# PET_snes_gamepad.net
KiCad netlist of a schematic drawn in EAGLE
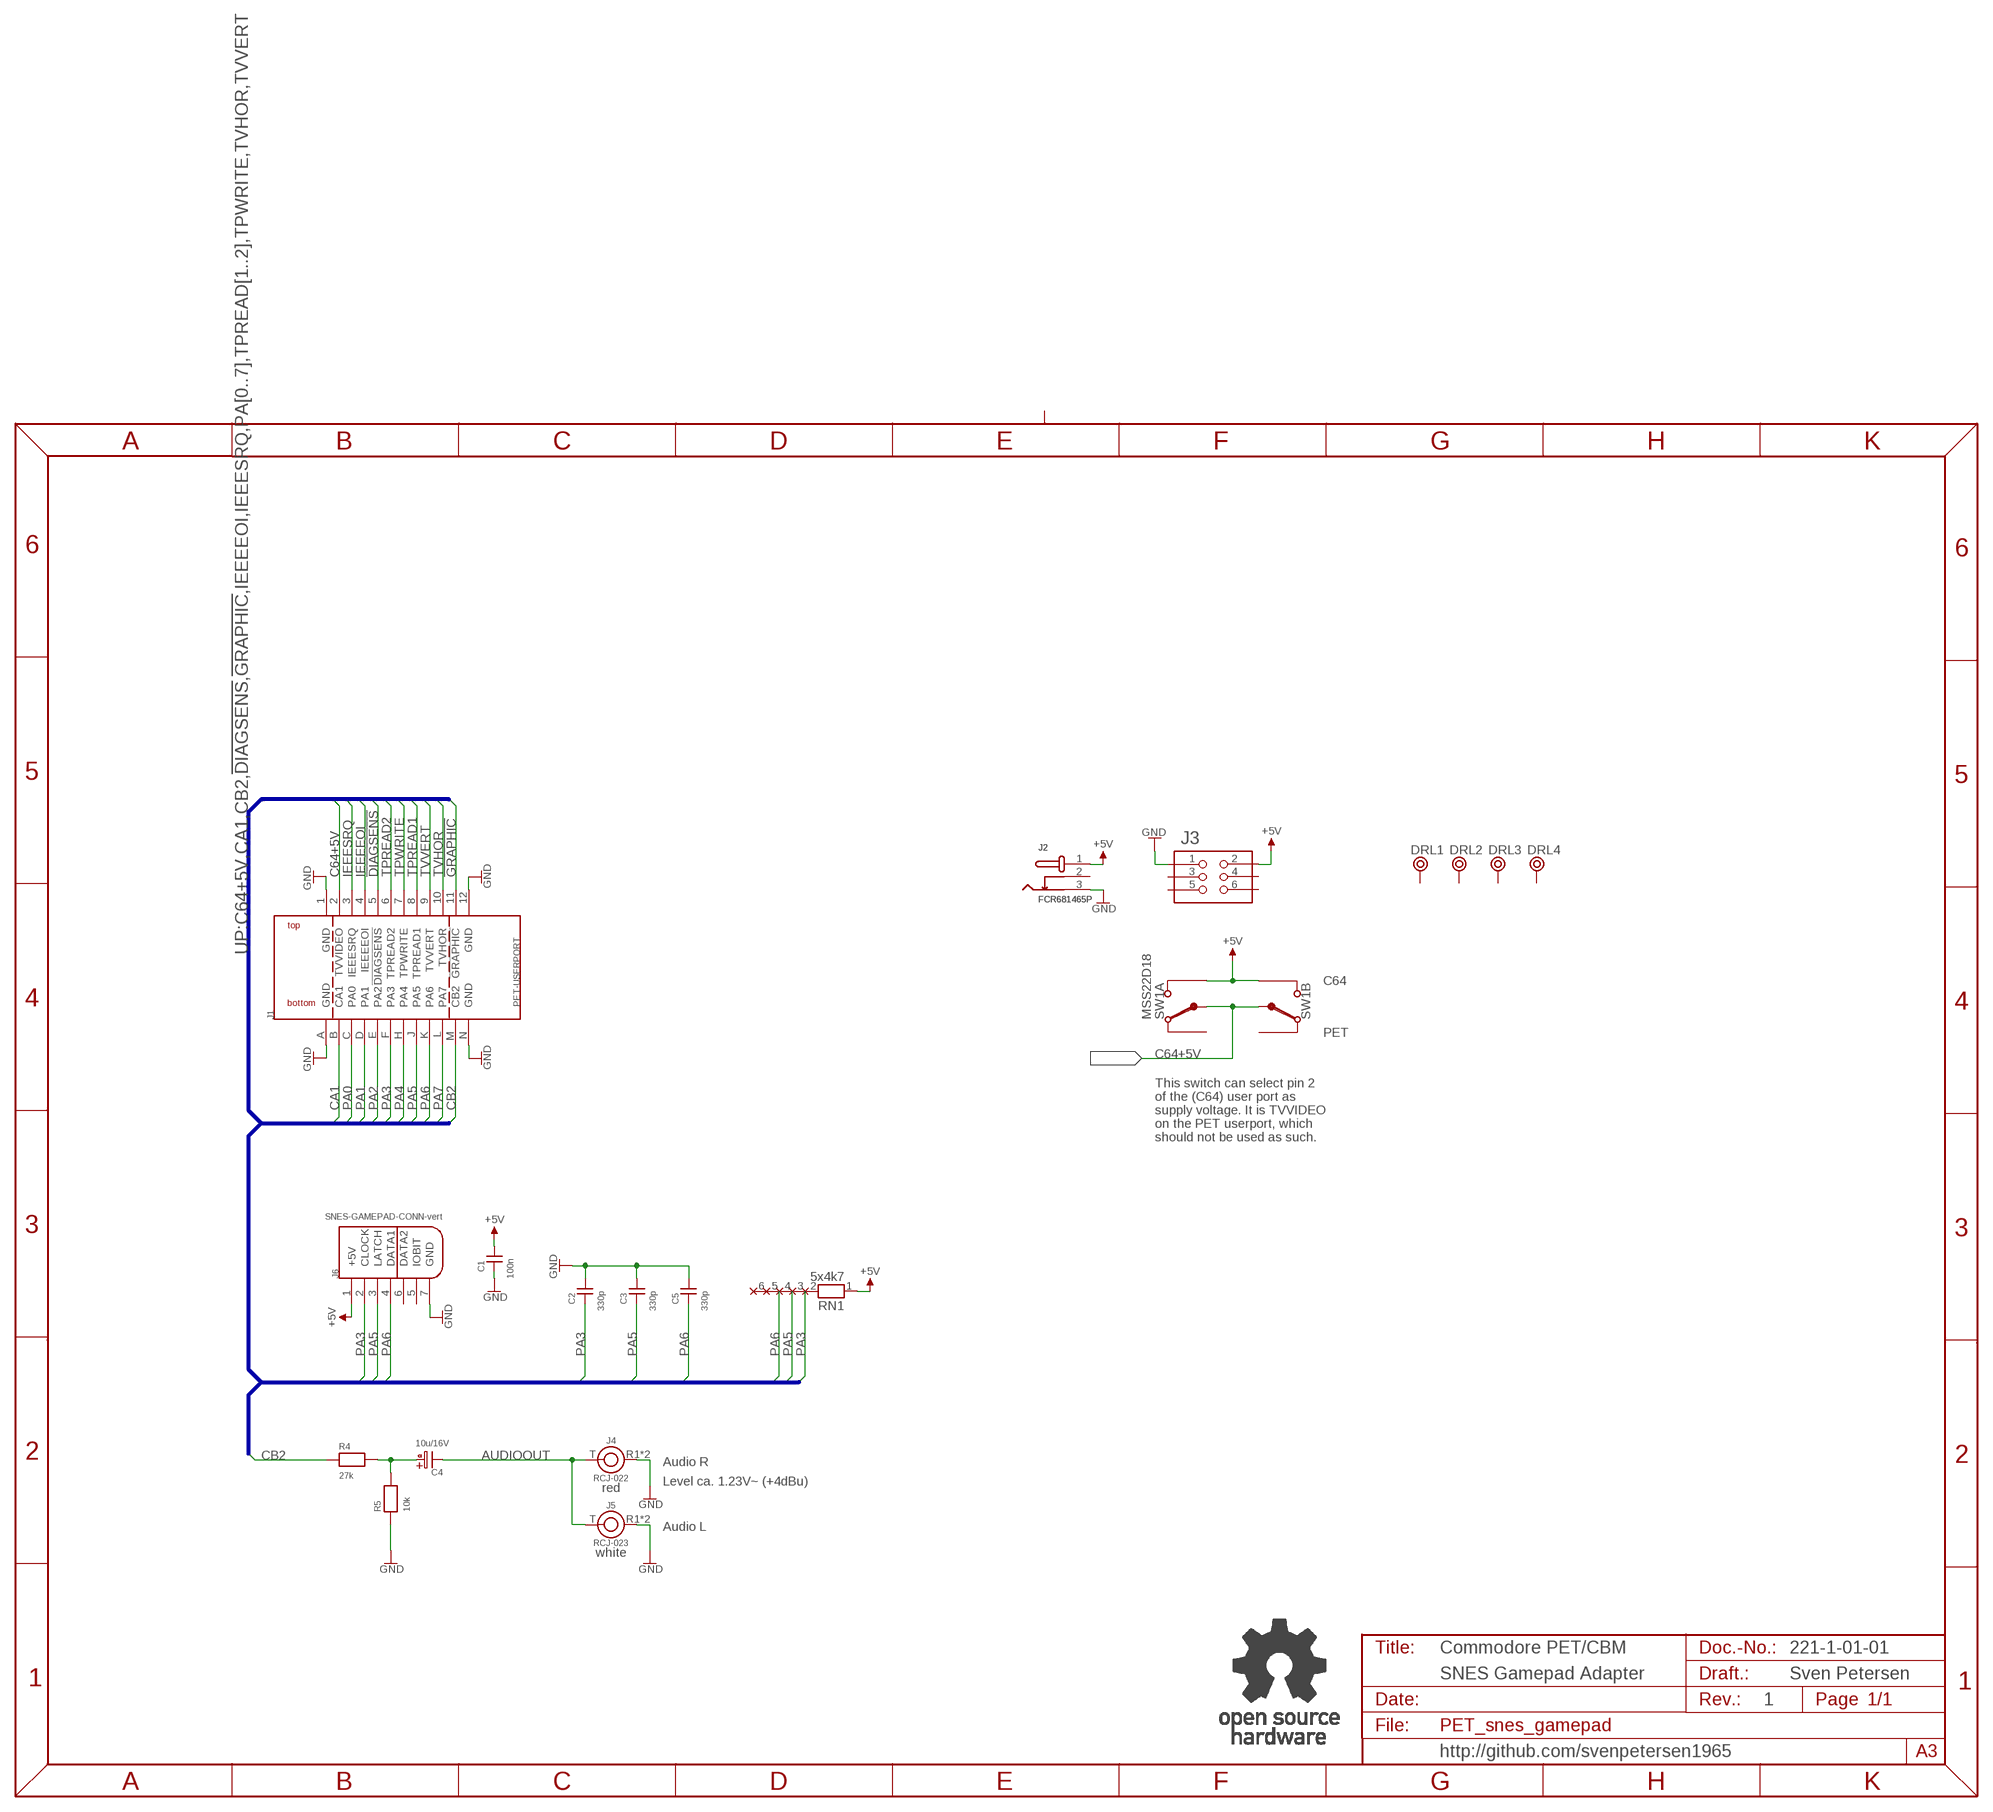
[diagram p0: schematic, sheet 1]

(export (version "E")
  (design (tool "Eeschema 10.0.6"))
  (components
    (comp (ref "C1")
      (value "100n")
      (footprint "eagle-import:C-2,5")
      (libsource (lib "eagle-import") (part "CAP01"))
    )
    (comp (ref "C2")
      (value "330p")
      (footprint "eagle-import:C-2,5")
      (libsource (lib "eagle-import") (part "CAP01"))
    )
    (comp (ref "C3")
      (value "330p")
      (footprint "eagle-import:C-2,5")
      (libsource (lib "eagle-import") (part "CAP01"))
    )
    (comp (ref "C4")
      (value "10u/16V")
      (footprint "eagle-import:C5,0_2,0")
      (libsource (lib "eagle-import") (part "C05,0/2,0"))
    )
    (comp (ref "C5")
      (value "330p")
      (footprint "eagle-import:C-2,5")
      (libsource (lib "eagle-import") (part "CAP01"))
    )
    (comp (ref "DRL1")
      (value "BOHR3,5")
      (footprint "eagle-import:BOHR3,5")
      (libsource (lib "eagle-import") (part "BOHR3,5"))
    )
    (comp (ref "DRL2")
      (value "BOHR3,5")
      (footprint "eagle-import:BOHR3,5")
      (libsource (lib "eagle-import") (part "BOHR3,5"))
    )
    (comp (ref "DRL3")
      (value "BOHR3,5")
      (footprint "eagle-import:BOHR3,5")
      (libsource (lib "eagle-import") (part "BOHR3,5"))
    )
    (comp (ref "DRL4")
      (value "BOHR3,5")
      (footprint "eagle-import:BOHR3,5")
      (libsource (lib "eagle-import") (part "BOHR3,5"))
    )
    (comp (ref "J1")
      (value "PET-USERPORT")
      (footprint "eagle-import:USERPORT")
      (libsource (lib "eagle-import") (part "PET-USERPORT"))
    )
    (comp (ref "J2")
      (value "FCR681465P")
      (footprint "eagle-import:FCR681465P")
      (libsource (lib "eagle-import") (part "FCR681465P"))
    )
    (comp (ref "J3")
      (value "2X03WV")
      (footprint "eagle-import:2X03WV")
      (libsource (lib "eagle-import") (part "2X03WV"))
    )
    (comp (ref "J4")
      (value "RCJ-022")
      (footprint "eagle-import:RCJ-02X")
      (libsource (lib "eagle-import") (part "RCJ-02X"))
    )
    (comp (ref "J5")
      (value "RCJ-023")
      (footprint "eagle-import:RCJ-02X")
      (libsource (lib "eagle-import") (part "RCJ-02X"))
    )
    (comp (ref "J6")
      (value "SNES-GAMEPAD-CONN-vert")
      (footprint "eagle-import:SNES_GAMEPAD_VERT")
      (libsource (lib "eagle-import") (part "GAMEPAD-CONN_SNESCONN"))
    )
    (comp (ref "R4")
      (value "27k")
      (footprint "eagle-import:R-10")
      (libsource (lib "eagle-import") (part "RES04"))
    )
    (comp (ref "R5")
      (value "10k")
      (footprint "eagle-import:R-10")
      (libsource (lib "eagle-import") (part "RES04"))
    )
    (comp (ref "RN1")
      (value "5x4k7")
      (footprint "eagle-import:RN-6")
      (libsource (lib "eagle-import") (part "RN05"))
    )
    (comp (ref "SW1")
      (value "MSS22D18")
      (footprint "eagle-import:DPDT_9MM")
      (libsource (lib "eagle-import") (part "DPDT_9MM"))
    )
    (comp (ref "U$2")
      (value "OPEN_SOURCE_HW")
      (footprint "eagle-import:OPENHW")
      (libsource (lib "eagle-import") (part "OPEN_SOURCE_HW"))
    )
  )
  (nets
    (net (code "2") (name "+5V") (class "Default")
      (node (ref "C1") (pin "2") (pinfunction "2_2") (pintype "passive"))
      (node (ref "J2") (pin "1") (pinfunction "1_1") (pintype "bidirectional"))
      (node (ref "J3") (pin "2") (pinfunction "2_2") (pintype "passive"))
      (node (ref "J6") (pin "1") (pinfunction "+5V_1") (pintype "power_in"))
      (node (ref "RN1") (pin "1") (pinfunction "1_1") (pintype "passive"))
      (node (ref "SW1") (pin "1") (pinfunction "UP_1") (pintype "bidirectional"))
      (node (ref "SW1") (pin "6") (pinfunction "UP_6") (pintype "bidirectional"))
    )
    (net (code "3") (name "/AUDIOOUT") (class "Default")
      (node (ref "C4") (pin "K") (pinfunction "-_K") (pintype "passive"))
      (node (ref "J4") (pin "T") (pinfunction "T_T") (pintype "bidirectional"))
      (node (ref "J5") (pin "T") (pinfunction "T_T") (pintype "bidirectional"))
    )
    (net (code "4") (name "/C64+5V") (class "Default")
      (node (ref "J1") (pin "2") (pinfunction "TVVIDEO_2") (pintype "output"))
      (node (ref "SW1") (pin "2") (pinfunction "COM_2") (pintype "bidirectional"))
      (node (ref "SW1") (pin "5") (pinfunction "COM_5") (pintype "bidirectional"))
    )
    (net (code "5") (name "/CA1") (class "Default")
      (node (ref "J1") (pin "B") (pinfunction "CA1_B") (pintype "input"))
    )
    (net (code "6") (name "/CB2") (class "Default")
      (node (ref "J1") (pin "M") (pinfunction "CB2_M") (pintype "bidirectional"))
      (node (ref "R4") (pin "1") (pinfunction "1_1") (pintype "passive"))
    )
    (net (code "7") (name "/IEEEEOI") (class "Default")
      (node (ref "J1") (pin "4") (pinfunction "IEEEEOI_4") (pintype "output"))
    )
    (net (code "8") (name "/IEEESRQ") (class "Default")
      (node (ref "J1") (pin "3") (pinfunction "IEEESRQ_3") (pintype "output"))
    )
    (net (code "9") (name "/PA0") (class "Default")
      (node (ref "J1") (pin "C") (pinfunction "PA0_C") (pintype "bidirectional"))
    )
    (net (code "10") (name "/PA1") (class "Default")
      (node (ref "J1") (pin "D") (pinfunction "PA1_D") (pintype "bidirectional"))
    )
    (net (code "11") (name "/PA2") (class "Default")
      (node (ref "J1") (pin "E") (pinfunction "PA2_E") (pintype "bidirectional"))
    )
    (net (code "12") (name "/PA3") (class "Default")
      (node (ref "C2") (pin "1") (pinfunction "1_1") (pintype "passive"))
      (node (ref "J1") (pin "F") (pinfunction "PA3_F") (pintype "bidirectional"))
      (node (ref "J6") (pin "2") (pinfunction "CLOCK_2") (pintype "bidirectional"))
      (node (ref "RN1") (pin "2") (pinfunction "2_2") (pintype "passive"))
    )
    (net (code "13") (name "/PA4") (class "Default")
      (node (ref "J1") (pin "H") (pinfunction "PA4_H") (pintype "bidirectional"))
    )
    (net (code "14") (name "/PA5") (class "Default")
      (node (ref "C3") (pin "1") (pinfunction "1_1") (pintype "passive"))
      (node (ref "J1") (pin "J") (pinfunction "PA5_J") (pintype "bidirectional"))
      (node (ref "J6") (pin "3") (pinfunction "LATCH_3") (pintype "bidirectional"))
      (node (ref "RN1") (pin "3") (pinfunction "3_3") (pintype "passive"))
    )
    (net (code "15") (name "/PA6") (class "Default")
      (node (ref "C5") (pin "1") (pinfunction "1_1") (pintype "passive"))
      (node (ref "J1") (pin "K") (pinfunction "PA6_K") (pintype "bidirectional"))
      (node (ref "J6") (pin "4") (pinfunction "DATA1_4") (pintype "bidirectional"))
      (node (ref "RN1") (pin "4") (pinfunction "4_4") (pintype "passive"))
    )
    (net (code "16") (name "/PA7") (class "Default")
      (node (ref "J1") (pin "L") (pinfunction "PA7_L") (pintype "bidirectional"))
    )
    (net (code "17") (name "/TPREAD1") (class "Default")
      (node (ref "J1") (pin "8") (pinfunction "TPREAD1_8") (pintype "output"))
    )
    (net (code "18") (name "/TPREAD2") (class "Default")
      (node (ref "J1") (pin "6") (pinfunction "TPREAD2_6") (pintype "output"))
    )
    (net (code "19") (name "/TPWRITE") (class "Default")
      (node (ref "J1") (pin "7") (pinfunction "TPWRITE_7") (pintype "output"))
    )
    (net (code "20") (name "/TVHOR") (class "Default")
      (node (ref "J1") (pin "10") (pinfunction "TVHOR_10") (pintype "output"))
    )
    (net (code "21") (name "/TVVERT") (class "Default")
      (node (ref "J1") (pin "9") (pinfunction "TVVERT_9") (pintype "output"))
    )
    (net (code "23") (name "/~{DIAGSENS}") (class "Default")
      (node (ref "J1") (pin "5") (pinfunction "~{DIAGSENS}_5") (pintype "output"))
    )
    (net (code "24") (name "/~{GRAPHIC}") (class "Default")
      (node (ref "J1") (pin "11") (pinfunction "~{GRAPHIC}_11") (pintype "output"))
    )
    (net (code "25") (name "GND") (class "Default")
      (node (ref "C1") (pin "1") (pinfunction "1_1") (pintype "passive"))
      (node (ref "C2") (pin "2") (pinfunction "2_2") (pintype "passive"))
      (node (ref "C3") (pin "2") (pinfunction "2_2") (pintype "passive"))
      (node (ref "C5") (pin "2") (pinfunction "2_2") (pintype "passive"))
      (node (ref "J1") (pin "1") (pinfunction "GND_1") (pintype "power_in"))
      (node (ref "J1") (pin "12") (pinfunction "GND_12") (pintype "power_in"))
      (node (ref "J1") (pin "A") (pinfunction "GND_A") (pintype "power_in"))
      (node (ref "J1") (pin "N") (pinfunction "GND_N") (pintype "power_in"))
      (node (ref "J2") (pin "3") (pinfunction "3_3") (pintype "bidirectional"))
      (node (ref "J3") (pin "1") (pinfunction "1_1") (pintype "passive"))
      (node (ref "J4") (pin "R1") (pinfunction "R_R1") (pintype "bidirectional"))
      (node (ref "J4") (pin "R2") (pinfunction "R_R2") (pintype "bidirectional"))
      (node (ref "J5") (pin "R1") (pinfunction "R_R1") (pintype "bidirectional"))
      (node (ref "J5") (pin "R2") (pinfunction "R_R2") (pintype "bidirectional"))
      (node (ref "J6") (pin "7") (pinfunction "GND_7") (pintype "power_in"))
      (node (ref "R5") (pin "1") (pinfunction "1_1") (pintype "passive"))
    )
    (net (code "26") (name "Net-(C4-+)") (class "Default")
      (node (ref "C4") (pin "A") (pinfunction "+_A") (pintype "passive"))
      (node (ref "R4") (pin "2") (pinfunction "2_2") (pintype "passive"))
      (node (ref "R5") (pin "2") (pinfunction "2_2") (pintype "passive"))
    )
    (net (code "27") (name "unconnected-(DRL1-PadP$1)") (class "Default")
      (node (ref "DRL1") (pin "P$1") (pinfunction "P$1_P$1") (pintype "passive"))
    )
    (net (code "28") (name "unconnected-(DRL2-PadP$1)") (class "Default")
      (node (ref "DRL2") (pin "P$1") (pinfunction "P$1_P$1") (pintype "passive"))
    )
    (net (code "29") (name "unconnected-(DRL3-PadP$1)") (class "Default")
      (node (ref "DRL3") (pin "P$1") (pinfunction "P$1_P$1") (pintype "passive"))
    )
    (net (code "30") (name "unconnected-(DRL4-PadP$1)") (class "Default")
      (node (ref "DRL4") (pin "P$1") (pinfunction "P$1_P$1") (pintype "passive"))
    )
    (net (code "31") (name "unconnected-(J2-Pad2)") (class "Default")
      (node (ref "J2") (pin "2") (pinfunction "2_2") (pintype "bidirectional"))
    )
    (net (code "32") (name "unconnected-(J3-Pad3)") (class "Default")
      (node (ref "J3") (pin "3") (pinfunction "3_3") (pintype "passive"))
    )
    (net (code "33") (name "unconnected-(J3-Pad4)") (class "Default")
      (node (ref "J3") (pin "4") (pinfunction "4_4") (pintype "passive"))
    )
    (net (code "34") (name "unconnected-(J3-Pad5)") (class "Default")
      (node (ref "J3") (pin "5") (pinfunction "5_5") (pintype "passive"))
    )
    (net (code "35") (name "unconnected-(J3-Pad6)") (class "Default")
      (node (ref "J3") (pin "6") (pinfunction "6_6") (pintype "passive"))
    )
    (net (code "36") (name "unconnected-(J6-DATA2-Pad6)") (class "Default")
      (node (ref "J6") (pin "6") (pinfunction "DATA2_6") (pintype "bidirectional"))
    )
    (net (code "37") (name "unconnected-(J6-IOBIT-Pad5)") (class "Default")
      (node (ref "J6") (pin "5") (pinfunction "IOBIT_5") (pintype "bidirectional"))
    )
    (net (code "38") (name "unconnected-(RN1-Pad5)") (class "Default")
      (node (ref "RN1") (pin "5") (pinfunction "5_5") (pintype "passive"))
    )
    (net (code "39") (name "unconnected-(RN1-Pad6)") (class "Default")
      (node (ref "RN1") (pin "6") (pinfunction "6_6") (pintype "passive"))
    )
    (net (code "40") (name "unconnected-(SW1A-DWN-Pad3)") (class "Default")
      (node (ref "SW1") (pin "3") (pinfunction "DWN_3") (pintype "bidirectional"))
    )
    (net (code "41") (name "unconnected-(SW1B-DWN-Pad4)") (class "Default")
      (node (ref "SW1") (pin "4") (pinfunction "DWN_4") (pintype "bidirectional"))
    )
  )
)
